# 12V_Buck.net
KiCad netlist of a schematic drawn in Altium Designer
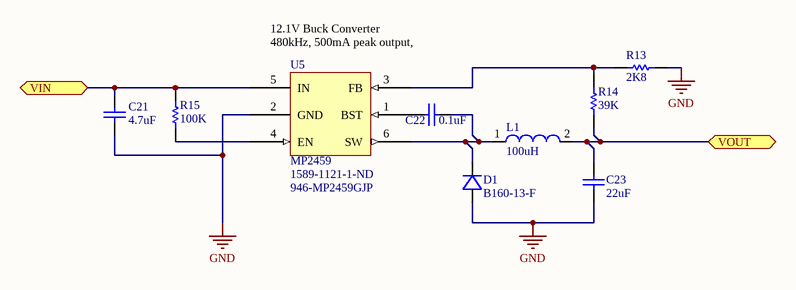
[diagram p0: 12V_Buck.SchDoc]

(export (version "E")
  (design (tool "Eeschema 10.0.6"))
  (components
    (comp (ref "C21")
      (value "4.7uF")
      (footprint "CAPC1210(3225)280_L")
      (description "CAP 4.7uF 50V ±20% 1210 (3225 Metric) Thickness 2.8mm SMD")
      (fields (field (name "TOLERANCE") "Â±20%"))
      (libsource (lib "Altium Content Vault") (part "CMP-1038-02163-1"))
    )
    (comp (ref "C22")
      (value "0.1uF")
      (footprint "CAPC0603(1608)100_L")
      (description "CAP 100nF 100V ±10% 0603 (1608 Metric) Thickness 1mm SMD")
      (fields (field (name "TOLERANCE") "Â±10%"))
      (libsource (lib "Altium Content Vault") (part "CMP-1035-02595-1"))
    )
    (comp (ref "C23")
      (value "22uF")
      (footprint "CAPC1210(3225)210_L")
      (description "CAP 22uF 16V ±20% 1210 (3225 Metric) Thickness 2.05mm SMD")
      (fields (field (name "TOLERANCE") "Â±20%"))
      (libsource (lib "Altium Content Vault") (part "CMP-1038-02278-1"))
    )
    (comp (ref "D1")
      (value "B160-13-F")
      (footprint "DO-214AC")
      (libsource (lib "Components") (part "B160-13-F"))
    )
    (comp (ref "L1")
      (value "100uH")
      (footprint "WE-PD-XS-PB")
      (description "SMD-Shielded Power Inductor WE-PD, L = 100 µH")
      (libsource (lib "Altium Content Vault") (part "PAS-IND-INDUCTOR-2"))
    )
    (comp (ref "R13")
      (value "2K8")
      (footprint "RESC0603(1608)_L")
      (description "2K8 0.1W 1% 0603 (1608 Metric)  SMD")
      (fields (field (name "TOLERANCE") "1 %") (field (name "POWER") "0.1 W"))
      (libsource (lib "Altium Content Vault") (part "RES"))
    )
    (comp (ref "R14")
      (value "39K")
      (footprint "RESC0603(1608)_L")
      (description "39K 0.1W 1% 0603 (1608 Metric)  SMD")
      (fields (field (name "TOLERANCE") "1 %") (field (name "POWER") "0.1 W"))
      (libsource (lib "Altium Content Vault") (part "RES"))
    )
    (comp (ref "R15")
      (value "100K")
      (footprint "RESC0603(1608)_L")
      (description "100K 0.1W 1% 0603 (1608 Metric)  SMD")
      (fields (field (name "POWER") "0.1 W") (field (name "TOLERANCE") "1 %"))
      (libsource (lib "Altium Content Vault") (part "RES"))
    )
    (comp (ref "U5")
      (value "MP2459")
      (footprint "TSOT23-6")
      (fields
        (field (name "SUPPLIER PART NUMBER 1") "1589-1121-1-ND")
        (field (name "SUPPLIER PART NUMBER 2") "946-MP2459GJP")
      )
      (libsource (lib "Components") (part "MP2459"))
    )
  )
  (nets
    (net (code "1") (name "/VIN") (class "Default")
      (node (ref "C21") (pin "2") (pinfunction "2_2") (pintype "passive"))
      (node (ref "R15") (pin "2") (pinfunction "2_2") (pintype "passive"))
      (node (ref "U5") (pin "5") (pinfunction "IN_5") (pintype "power_in"))
    )
    (net (code "2") (name "/VOUT") (class "Default")
      (node (ref "C23") (pin "2") (pinfunction "2_2") (pintype "passive"))
      (node (ref "L1") (pin "2") (pinfunction "2_2") (pintype "passive"))
      (node (ref "R14") (pin "2") (pinfunction "2_2") (pintype "passive"))
    )
    (net (code "3") (name "GND") (class "Default")
      (node (ref "C21") (pin "1") (pinfunction "1_1") (pintype "passive"))
      (node (ref "C23") (pin "1") (pinfunction "1_1") (pintype "passive"))
      (node (ref "D1") (pin "2") (pinfunction "A_2") (pintype "passive"))
      (node (ref "R13") (pin "1") (pinfunction "1_1") (pintype "passive"))
      (node (ref "U5") (pin "2") (pinfunction "GND_2") (pintype "power_in"))
    )
    (net (code "4") (name "Net-(D1-K)") (class "Default")
      (node (ref "C22") (pin "2") (pinfunction "2_2") (pintype "passive"))
      (node (ref "D1") (pin "1") (pinfunction "K_1") (pintype "passive"))
      (node (ref "L1") (pin "1") (pinfunction "1_1") (pintype "passive"))
      (node (ref "U5") (pin "6") (pinfunction "SW_6") (pintype "output"))
    )
    (net (code "5") (name "Net-(U5-BST)") (class "Default")
      (node (ref "C22") (pin "1") (pinfunction "1_1") (pintype "passive"))
      (node (ref "U5") (pin "1") (pinfunction "BST_1") (pintype "input"))
    )
    (net (code "6") (name "Net-(U5-EN)") (class "Default")
      (node (ref "R15") (pin "1") (pinfunction "1_1") (pintype "passive"))
      (node (ref "U5") (pin "4") (pinfunction "EN_4") (pintype "input"))
    )
    (net (code "7") (name "Net-(U5-FB)") (class "Default")
      (node (ref "R13") (pin "2") (pinfunction "2_2") (pintype "passive"))
      (node (ref "R14") (pin "1") (pinfunction "1_1") (pintype "passive"))
      (node (ref "U5") (pin "3") (pinfunction "FB_3") (pintype "input"))
    )
  )
)
